# socket.net
KiCad netlist of a schematic drawn in Altium Designer
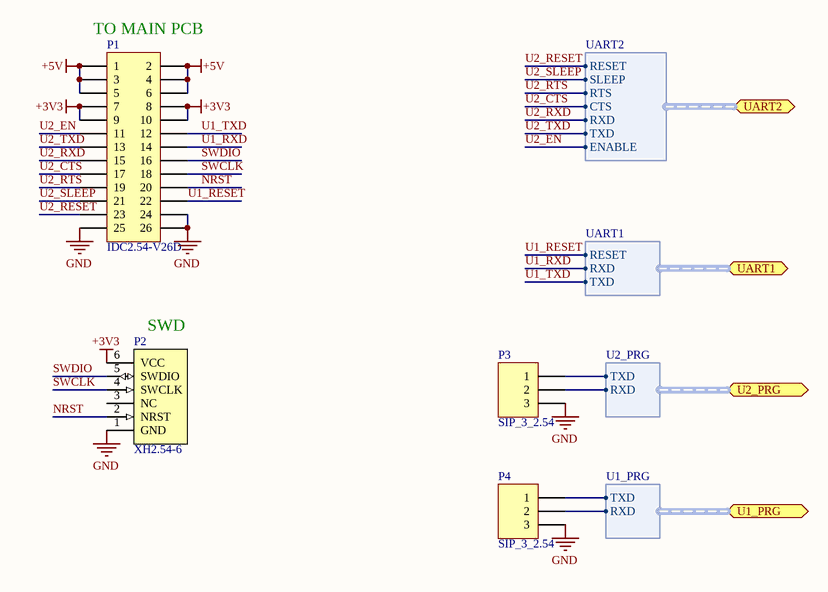
[diagram p0: socket.SchDoc]

(export (version "E")
  (design (tool "Eeschema 10.0.6"))
  (components
    (comp (ref "P1")
      (value "IDC2.54-V26D")
      (footprint "Con IDC:IDC2.54-V26D")
      (description "IDC2.54-13x2 Header")
      (fields (field (name "PUBLISHER") "Altium Limited"))
      (libsource (lib "Miscellaneous Connectors") (part "Header 13X2"))
    )
    (comp (ref "P2")
      (value "XH2.54-6")
      (footprint "UserPcbLib:REAL_SIP6_2.54")
      (description "SW debug connector")
      (libsource (lib "UserSchlib") (part "SWD-Connector"))
    )
    (comp (ref "P3")
      (value "SIP_3_2.54")
      (footprint "UserPcbLib:REAL_SIP3_2.54")
      (description "Header, 3-Pin")
      (fields (field (name "PUBLISHER") "Altium Limited"))
      (libsource (lib "Miscellaneous Connectors") (part "Header 3"))
    )
    (comp (ref "P4")
      (value "SIP_3_2.54")
      (footprint "UserPcbLib:REAL_SIP3_2.54")
      (description "Header, 3-Pin")
      (fields (field (name "PUBLISHER") "Altium Limited"))
      (libsource (lib "Miscellaneous Connectors") (part "Header 3"))
    )
  )
  (nets
    (net (code "5") (name "+3V3") (class "Default")
      (node (ref "P1") (pin "10") (pinfunction "10_10") (pintype "passive"))
      (node (ref "P1") (pin "7") (pinfunction "7_7") (pintype "passive"))
      (node (ref "P1") (pin "8") (pinfunction "8_8") (pintype "passive"))
      (node (ref "P1") (pin "9") (pinfunction "9_9") (pintype "passive"))
      (node (ref "P2") (pin "6") (pinfunction "VCC_6") (pintype "power_in"))
    )
    (net (code "6") (name "+5V") (class "Default")
      (node (ref "P1") (pin "1") (pinfunction "1_1") (pintype "passive"))
      (node (ref "P1") (pin "2") (pinfunction "2_2") (pintype "passive"))
      (node (ref "P1") (pin "3") (pinfunction "3_3") (pintype "passive"))
      (node (ref "P1") (pin "4") (pinfunction "4_4") (pintype "passive"))
      (node (ref "P1") (pin "5") (pinfunction "5_5") (pintype "passive"))
      (node (ref "P1") (pin "6") (pinfunction "6_6") (pintype "passive"))
    )
    (net (code "7") (name "/NRST") (class "Default")
      (node (ref "P1") (pin "20") (pinfunction "20_20") (pintype "passive"))
      (node (ref "P2") (pin "2") (pinfunction "NRST_2") (pintype "input"))
    )
    (net (code "8") (name "/SWCLK") (class "Default")
      (node (ref "P1") (pin "18") (pinfunction "18_18") (pintype "passive"))
      (node (ref "P2") (pin "4") (pinfunction "SWCLK_4") (pintype "input"))
    )
    (net (code "9") (name "/SWDIO") (class "Default")
      (node (ref "P1") (pin "16") (pinfunction "16_16") (pintype "passive"))
      (node (ref "P2") (pin "5") (pinfunction "SWDIO_5") (pintype "bidirectional"))
    )
    (net (code "10") (name "/U1_RESET") (class "Default")
      (node (ref "P1") (pin "22") (pinfunction "22_22") (pintype "passive"))
    )
    (net (code "11") (name "/U1_RXD") (class "Default")
      (node (ref "P1") (pin "14") (pinfunction "14_14") (pintype "passive"))
    )
    (net (code "12") (name "/U1_TXD") (class "Default")
      (node (ref "P1") (pin "12") (pinfunction "12_12") (pintype "passive"))
    )
    (net (code "13") (name "/U2_CTS") (class "Default")
      (node (ref "P1") (pin "17") (pinfunction "17_17") (pintype "passive"))
    )
    (net (code "14") (name "/U2_EN") (class "Default")
      (node (ref "P1") (pin "11") (pinfunction "11_11") (pintype "passive"))
    )
    (net (code "15") (name "/U2_RESET") (class "Default")
      (node (ref "P1") (pin "23") (pinfunction "23_23") (pintype "passive"))
    )
    (net (code "16") (name "/U2_RTS") (class "Default")
      (node (ref "P1") (pin "19") (pinfunction "19_19") (pintype "passive"))
    )
    (net (code "17") (name "/U2_RXD") (class "Default")
      (node (ref "P1") (pin "15") (pinfunction "15_15") (pintype "passive"))
    )
    (net (code "18") (name "/U2_SLEEP") (class "Default")
      (node (ref "P1") (pin "21") (pinfunction "21_21") (pintype "passive"))
    )
    (net (code "19") (name "/U2_TXD") (class "Default")
      (node (ref "P1") (pin "13") (pinfunction "13_13") (pintype "passive"))
    )
    (net (code "24") (name "GND") (class "Default")
      (node (ref "P1") (pin "24") (pinfunction "24_24") (pintype "passive"))
      (node (ref "P1") (pin "25") (pinfunction "25_25") (pintype "passive"))
      (node (ref "P1") (pin "26") (pinfunction "26_26") (pintype "passive"))
      (node (ref "P2") (pin "1") (pinfunction "GND_1") (pintype "power_in"))
      (node (ref "P3") (pin "3") (pinfunction "3_3") (pintype "passive"))
      (node (ref "P4") (pin "3") (pinfunction "3_3") (pintype "passive"))
    )
    (net (code "25") (name "unconnected-(P2-NC-Pad3)") (class "Default")
      (node (ref "P2") (pin "3") (pinfunction "NC_3") (pintype "power_in"))
    )
    (net (code "26") (name "unconnected-(P3-Pad1)") (class "Default")
      (node (ref "P3") (pin "1") (pinfunction "1_1") (pintype "passive"))
    )
    (net (code "27") (name "unconnected-(P3-Pad2)") (class "Default")
      (node (ref "P3") (pin "2") (pinfunction "2_2") (pintype "passive"))
    )
    (net (code "28") (name "unconnected-(P4-Pad1)") (class "Default")
      (node (ref "P4") (pin "1") (pinfunction "1_1") (pintype "passive"))
    )
    (net (code "29") (name "unconnected-(P4-Pad2)") (class "Default")
      (node (ref "P4") (pin "2") (pinfunction "2_2") (pintype "passive"))
    )
  )
)
